# MB1297_Arduino.net
KiCad netlist of a schematic drawn in Altium Designer
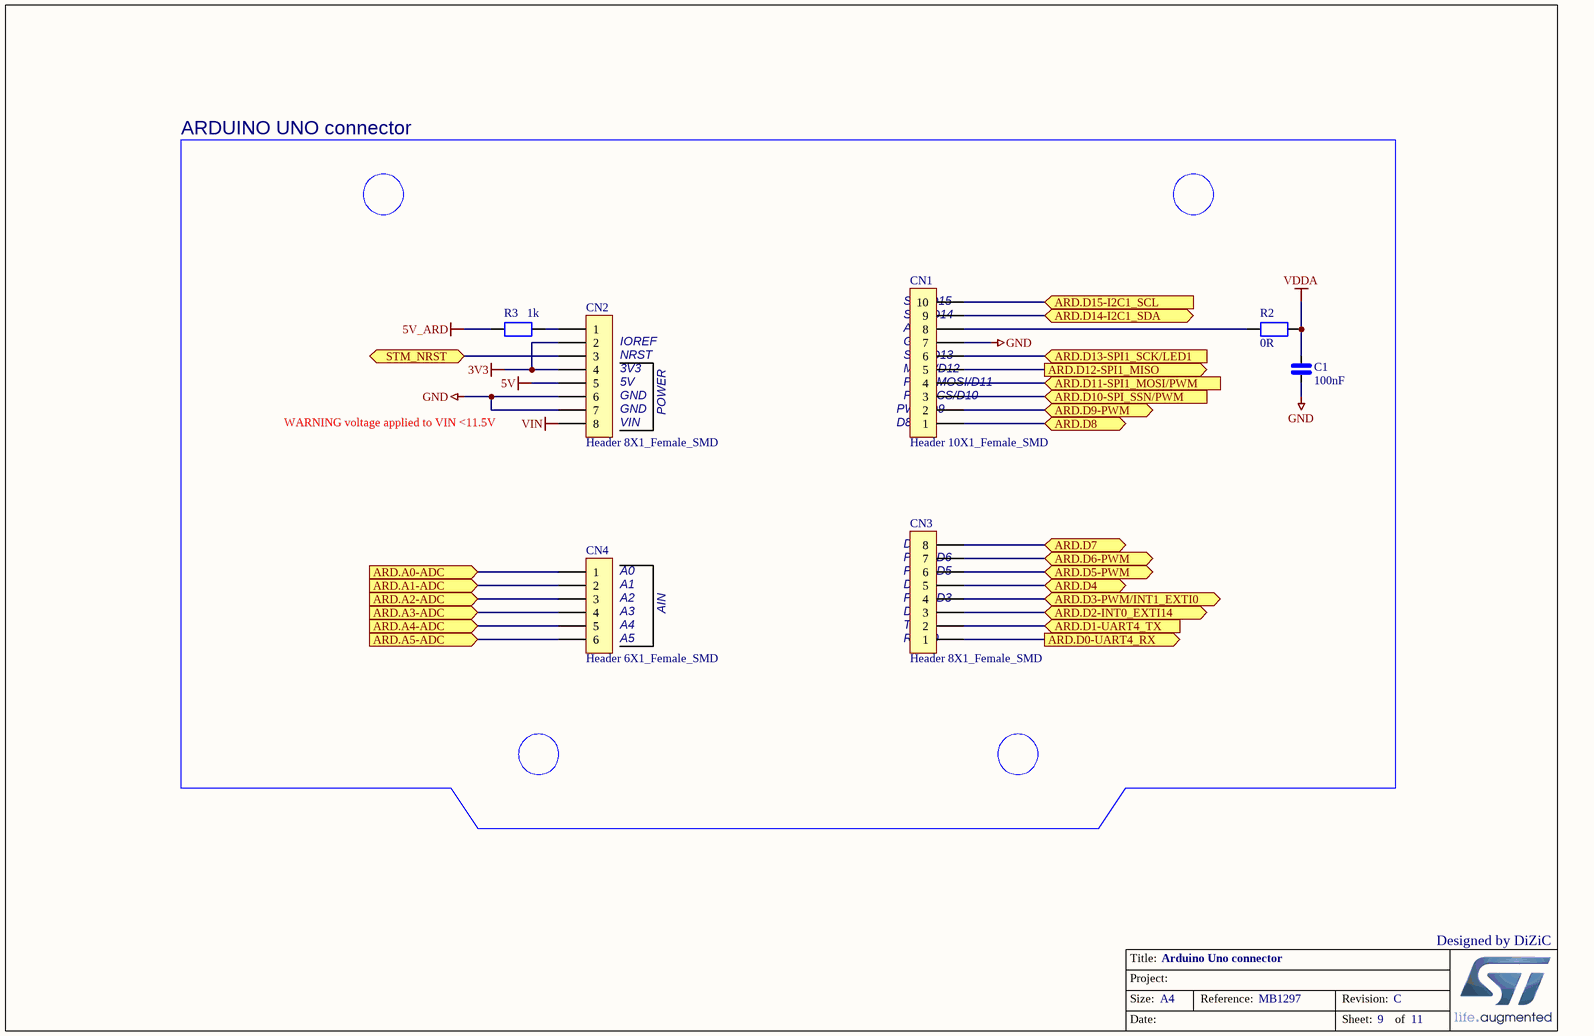
[diagram p0: MB1297_Arduino.SchDoc]

(export (version "E")
  (design (tool "Eeschema 10.0.6"))
  (components
    (comp (ref "C1")
      (value "100nF")
      (footprint "0402_CAP_NPOL")
      (description "Capacitor_not polarized")
      (libsource (lib "ST_Lib3D") (part "CAP_NPOL"))
    )
    (comp (ref "CN1")
      (value "Header 10X1_Female_SMD")
      (footprint "F-V50XC-1X10R-LF")
      (description "Header, 10-Pin, SMD, Single row,female")
      (fields (field (name "PUBLISHER") "Altium Limited"))
      (libsource (lib "ST_Lib3D") (part "Header 10X1_Female_SMD"))
    )
    (comp (ref "CN2")
      (value "Header 8X1_Female_SMD")
      (footprint "F-V50XC-1X08R-LF")
      (description "Header, 8-Pin, SMD, Single row,female")
      (fields (field (name "PUBLISHER") "Altium Limited"))
      (libsource (lib "") (part "Header 8X1_Female_SMD_1"))
    )
    (comp (ref "CN3")
      (value "Header 8X1_Female_SMD")
      (footprint "F-V50XC-1X08R-LF")
      (description "Header, 8-Pin, SMD, Single row,female")
      (fields (field (name "PUBLISHER") "Altium Limited"))
      (libsource (lib "ST_Lib3D") (part "Header 8X1_Female_SMD"))
    )
    (comp (ref "CN4")
      (value "Header 6X1_Female_SMD")
      (footprint "F-V50XC-1X06R-LF")
      (description "Header, 6-Pin, SMD, Single row,female")
      (fields (field (name "PUBLISHER") "Altium Limited"))
      (libsource (lib "ST_Lib3D") (part "Header 6X1_Female_SMD"))
    )
    (comp (ref "R2")
      (value "0R")
      (footprint "0402_RES")
      (description "Resistor")
      (libsource (lib "Lib3D_Altium10_Schlib") (part "RES"))
    )
    (comp (ref "R3")
      (value "1k")
      (footprint "0402_RES")
      (description "Resistor")
      (libsource (lib "Lib3D_Altium10_Schlib") (part "RES"))
    )
  )
  (nets
    (net (code "1") (name "/ARD.A0-ADC") (class "Default")
      (node (ref "CN4") (pin "1") (pinfunction "1_1") (pintype "passive"))
    )
    (net (code "2") (name "/ARD.A1-ADC") (class "Default")
      (node (ref "CN4") (pin "2") (pinfunction "2_2") (pintype "passive"))
    )
    (net (code "3") (name "/ARD.A2-ADC") (class "Default")
      (node (ref "CN4") (pin "3") (pinfunction "3_3") (pintype "passive"))
    )
    (net (code "4") (name "/ARD.A3-ADC") (class "Default")
      (node (ref "CN4") (pin "4") (pinfunction "4_4") (pintype "passive"))
    )
    (net (code "5") (name "/ARD.A4-ADC") (class "Default")
      (node (ref "CN4") (pin "5") (pinfunction "5_5") (pintype "passive"))
    )
    (net (code "6") (name "/ARD.A5-ADC") (class "Default")
      (node (ref "CN4") (pin "6") (pinfunction "6_6") (pintype "passive"))
    )
    (net (code "7") (name "/ARD.D0-UART4_RX") (class "Default")
      (node (ref "CN3") (pin "1") (pinfunction "1_1") (pintype "passive"))
    )
    (net (code "8") (name "/ARD.D1-UART4_TX") (class "Default")
      (node (ref "CN3") (pin "2") (pinfunction "2_2") (pintype "passive"))
    )
    (net (code "9") (name "/ARD.D2-INT0_EXTI14") (class "Default")
      (node (ref "CN3") (pin "3") (pinfunction "3_3") (pintype "passive"))
    )
    (net (code "10") (name "/ARD.D3-PWM{slash}INT1_EXTI0") (class "Default")
      (node (ref "CN3") (pin "4") (pinfunction "4_4") (pintype "passive"))
    )
    (net (code "11") (name "/ARD.D4") (class "Default")
      (node (ref "CN3") (pin "5") (pinfunction "5_5") (pintype "passive"))
    )
    (net (code "12") (name "/ARD.D5-PWM") (class "Default")
      (node (ref "CN3") (pin "6") (pinfunction "6_6") (pintype "passive"))
    )
    (net (code "13") (name "/ARD.D6-PWM") (class "Default")
      (node (ref "CN3") (pin "7") (pinfunction "7_7") (pintype "passive"))
    )
    (net (code "14") (name "/ARD.D7") (class "Default")
      (node (ref "CN3") (pin "8") (pinfunction "8_8") (pintype "passive"))
    )
    (net (code "15") (name "/ARD.D8") (class "Default")
      (node (ref "CN1") (pin "1") (pinfunction "1_1") (pintype "passive"))
    )
    (net (code "16") (name "/ARD.D9-PWM") (class "Default")
      (node (ref "CN1") (pin "2") (pinfunction "2_2") (pintype "passive"))
    )
    (net (code "17") (name "/ARD.D10-SPI_SSN{slash}PWM") (class "Default")
      (node (ref "CN1") (pin "3") (pinfunction "3_3") (pintype "passive"))
    )
    (net (code "18") (name "/ARD.D11-SPI1_MOSI{slash}PWM") (class "Default")
      (node (ref "CN1") (pin "4") (pinfunction "4_4") (pintype "passive"))
    )
    (net (code "19") (name "/ARD.D12-SPI1_MISO") (class "Default")
      (node (ref "CN1") (pin "5") (pinfunction "5_5") (pintype "passive"))
    )
    (net (code "20") (name "/ARD.D13-SPI1_SCK{slash}LED1") (class "Default")
      (node (ref "CN1") (pin "6") (pinfunction "6_6") (pintype "passive"))
    )
    (net (code "21") (name "/ARD.D14-I2C1_SDA") (class "Default")
      (node (ref "CN1") (pin "9") (pinfunction "9_9") (pintype "passive"))
    )
    (net (code "22") (name "/ARD.D15-I2C1_SCL") (class "Default")
      (node (ref "CN1") (pin "10") (pinfunction "10_10") (pintype "passive"))
    )
    (net (code "23") (name "/STM_NRST") (class "Default")
      (node (ref "CN2") (pin "3") (pinfunction "3_3") (pintype "passive"))
    )
    (net (code "24") (name "3V3") (class "Default")
      (node (ref "CN2") (pin "2") (pinfunction "2_2") (pintype "passive"))
      (node (ref "CN2") (pin "4") (pinfunction "4_4") (pintype "passive"))
    )
    (net (code "25") (name "5V") (class "Default")
      (node (ref "CN2") (pin "5") (pinfunction "5_5") (pintype "passive"))
    )
    (net (code "26") (name "5V_ARD") (class "Default")
      (node (ref "R3") (pin "1") (pinfunction "1_1") (pintype "passive"))
    )
    (net (code "27") (name "GND") (class "Default")
      (node (ref "C1") (pin "2") (pinfunction "2_2") (pintype "passive"))
      (node (ref "CN1") (pin "7") (pinfunction "7_7") (pintype "passive"))
      (node (ref "CN2") (pin "6") (pinfunction "6_6") (pintype "passive"))
      (node (ref "CN2") (pin "7") (pinfunction "7_7") (pintype "passive"))
    )
    (net (code "28") (name "Net-(CN1-Pad8)") (class "Default")
      (node (ref "CN1") (pin "8") (pinfunction "8_8") (pintype "passive"))
      (node (ref "R2") (pin "1") (pinfunction "1_1") (pintype "passive"))
    )
    (net (code "29") (name "Net-(CN2-Pad1)") (class "Default")
      (node (ref "CN2") (pin "1") (pinfunction "1_1") (pintype "passive"))
      (node (ref "R3") (pin "2") (pinfunction "2_2") (pintype "passive"))
    )
    (net (code "30") (name "VDDA") (class "Default")
      (node (ref "C1") (pin "1") (pinfunction "1_1") (pintype "passive"))
      (node (ref "R2") (pin "2") (pinfunction "2_2") (pintype "passive"))
    )
    (net (code "31") (name "VIN") (class "Default")
      (node (ref "CN2") (pin "8") (pinfunction "8_8") (pintype "passive"))
    )
  )
)
